# ioboard-right.net
KiCad netlist of a schematic drawn in EAGLE
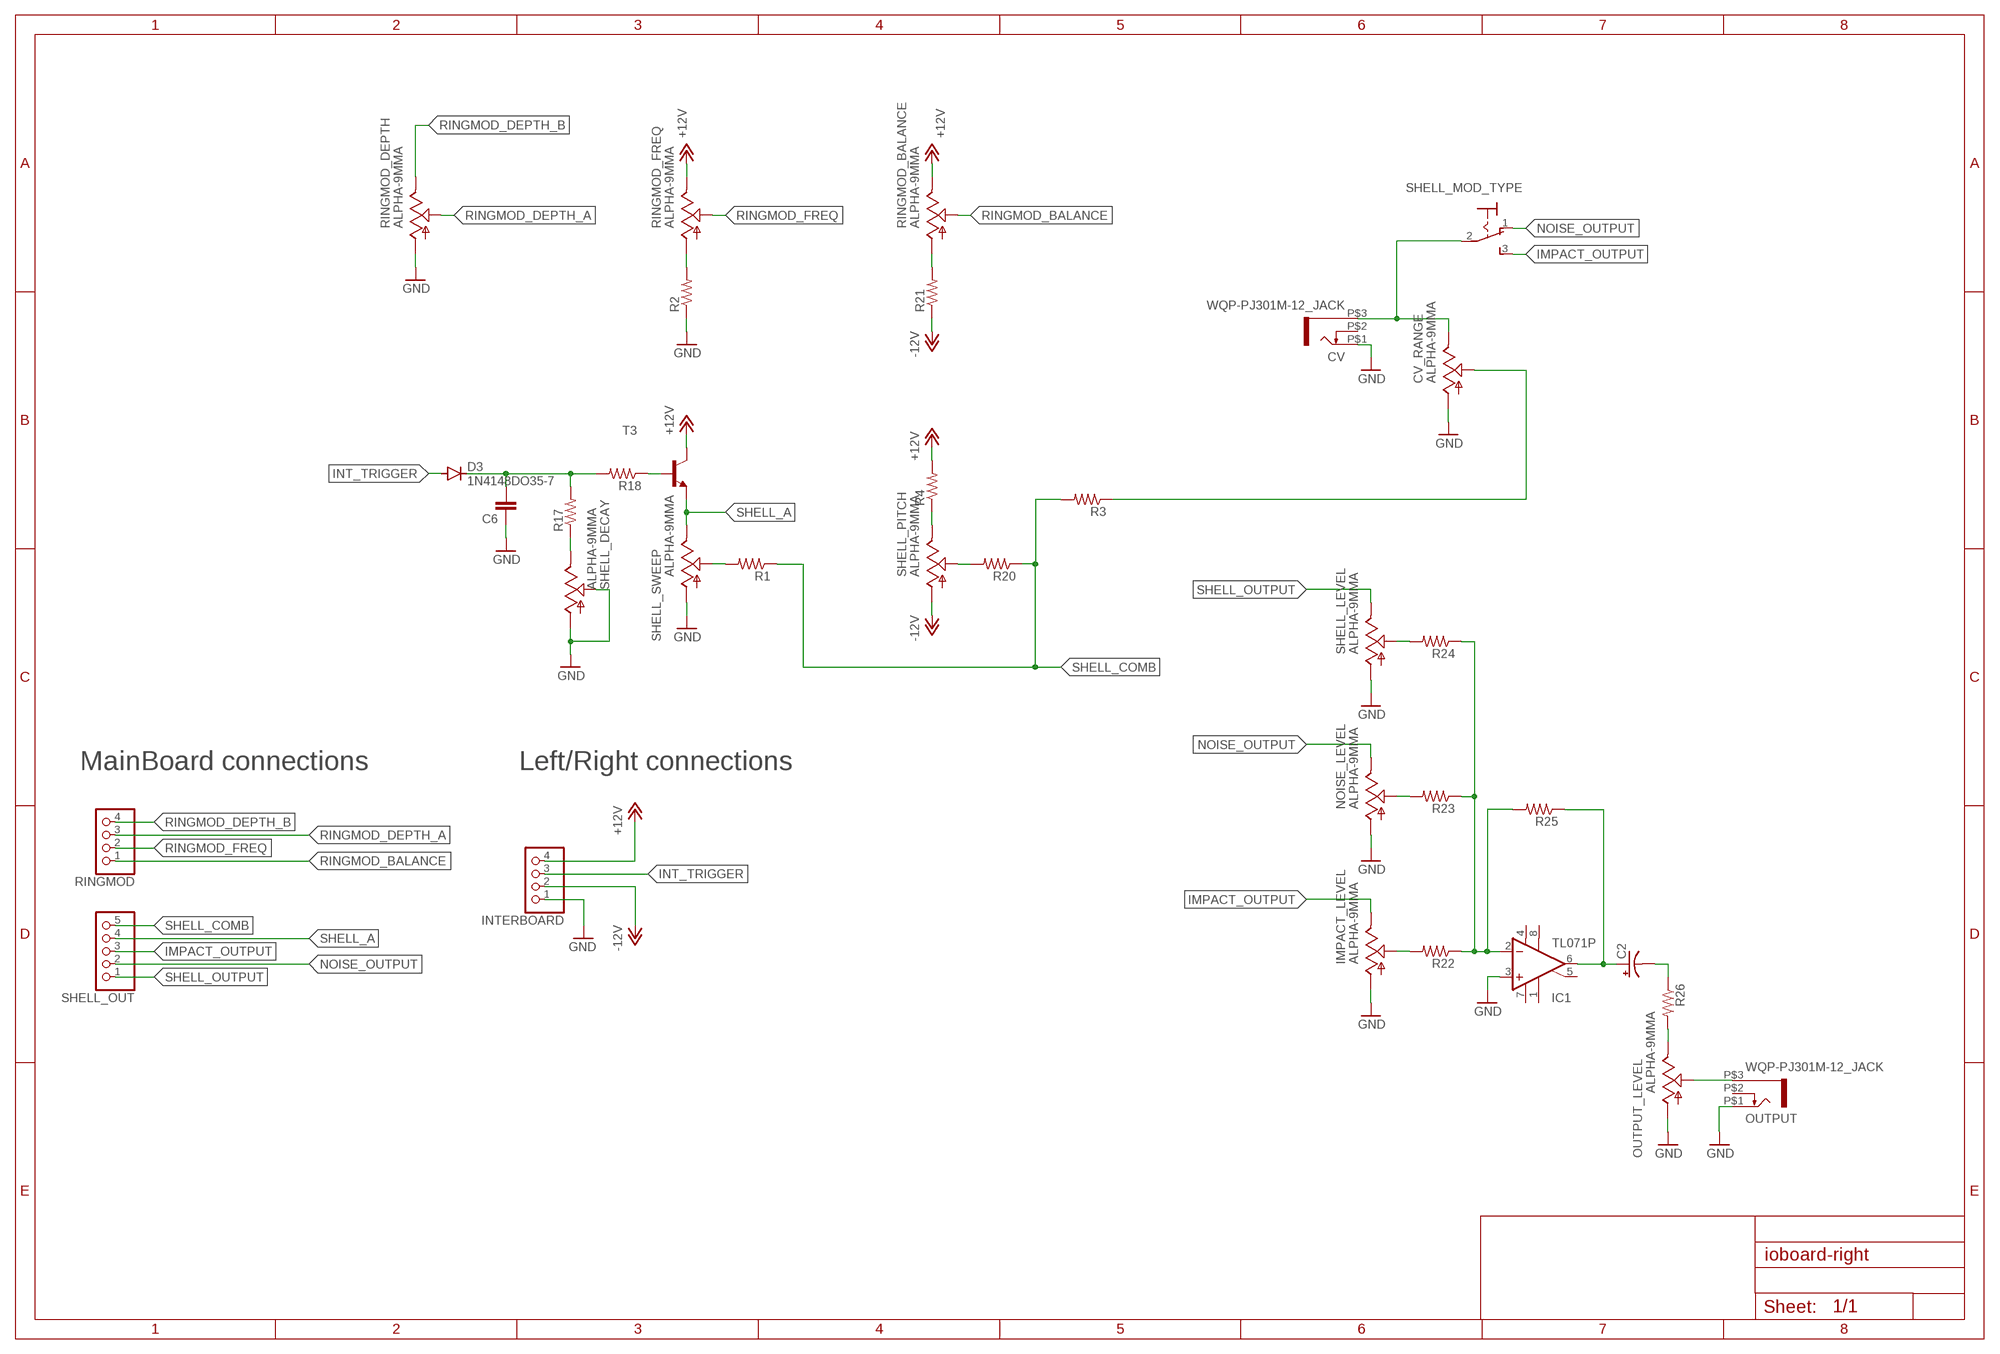
[diagram p0: schematic, sheet 1]

(export (version "E")
  (design (tool "Eeschema 10.0.6"))
  (components
    (comp (ref "C2")
      (value "CPOL-USE2.5-6")
      (footprint "eagle-import:E2,5-6")
      (libsource (lib "eagle-import") (part "CPOL-USE2.5-6"))
    )
    (comp (ref "C6")
      (value "C-EU050-024X044")
      (footprint "eagle-import:C050-024X044")
      (libsource (lib "eagle-import") (part "C-EU050-024X044"))
    )
    (comp (ref "CV")
      (value "WQP-PJ301M-12_JACK")
      (footprint "eagle-import:WQP-PJ301M-12_JACK")
      (libsource (lib "eagle-import") (part "WQP-PJ301M-12_JACK"))
    )
    (comp (ref "CV_RANGE")
      (value "ALPHA-9MMA")
      (footprint "eagle-import:EVUF")
      (libsource (lib "eagle-import") (part "ALPHA-9MMA"))
    )
    (comp (ref "D3")
      (value "1N4148DO35-7")
      (footprint "eagle-import:DO35-7")
      (libsource (lib "eagle-import") (part "1N4148DO35-7"))
    )
    (comp (ref "IC1")
      (value "TL071P")
      (footprint "eagle-import:DIL08")
      (libsource (lib "eagle-import") (part "TL071P"))
    )
    (comp (ref "IMPACT_LEVEL")
      (value "ALPHA-9MMA")
      (footprint "eagle-import:EVUF")
      (libsource (lib "eagle-import") (part "ALPHA-9MMA"))
    )
    (comp (ref "INTERBOARD")
      (value "PINHD-1X4")
      (footprint "eagle-import:1X04")
      (libsource (lib "eagle-import") (part "PINHD-1X4"))
    )
    (comp (ref "NOISE_LEVEL")
      (value "ALPHA-9MMA")
      (footprint "eagle-import:EVUF")
      (libsource (lib "eagle-import") (part "ALPHA-9MMA"))
    )
    (comp (ref "OUTPUT")
      (value "WQP-PJ301M-12_JACK")
      (footprint "eagle-import:WQP-PJ301M-12_JACK")
      (libsource (lib "eagle-import") (part "WQP-PJ301M-12_JACK"))
    )
    (comp (ref "OUTPUT_LEVEL")
      (value "ALPHA-9MMA")
      (footprint "eagle-import:EVUF")
      (libsource (lib "eagle-import") (part "ALPHA-9MMA"))
    )
    (comp (ref "R1")
      (value "R-US_0207/7")
      (footprint "eagle-import:0207_7")
      (libsource (lib "eagle-import") (part "R-US_0207/7"))
    )
    (comp (ref "R2")
      (value "R-US_0207/7")
      (footprint "eagle-import:0207_7")
      (libsource (lib "eagle-import") (part "R-US_0207/7"))
    )
    (comp (ref "R3")
      (value "R-US_0207/7")
      (footprint "eagle-import:0207_7")
      (libsource (lib "eagle-import") (part "R-US_0207/7"))
    )
    (comp (ref "R4")
      (value "R-US_0207/7")
      (footprint "eagle-import:0207_7")
      (libsource (lib "eagle-import") (part "R-US_0207/7"))
    )
    (comp (ref "R17")
      (value "R-US_0207/7")
      (footprint "eagle-import:0207_7")
      (libsource (lib "eagle-import") (part "R-US_0207/7"))
    )
    (comp (ref "R18")
      (value "R-US_0207/7")
      (footprint "eagle-import:0207_7")
      (libsource (lib "eagle-import") (part "R-US_0207/7"))
    )
    (comp (ref "R20")
      (value "R-US_0207/7")
      (footprint "eagle-import:0207_7")
      (libsource (lib "eagle-import") (part "R-US_0207/7"))
    )
    (comp (ref "R21")
      (value "R-US_0207/7")
      (footprint "eagle-import:0207_7")
      (libsource (lib "eagle-import") (part "R-US_0207/7"))
    )
    (comp (ref "R22")
      (value "R-US_0207/7")
      (footprint "eagle-import:0207_7")
      (libsource (lib "eagle-import") (part "R-US_0207/7"))
    )
    (comp (ref "R23")
      (value "R-US_0207/7")
      (footprint "eagle-import:0207_7")
      (libsource (lib "eagle-import") (part "R-US_0207/7"))
    )
    (comp (ref "R24")
      (value "R-US_0207/7")
      (footprint "eagle-import:0207_7")
      (libsource (lib "eagle-import") (part "R-US_0207/7"))
    )
    (comp (ref "R25")
      (value "R-US_0207/7")
      (footprint "eagle-import:0207_7")
      (libsource (lib "eagle-import") (part "R-US_0207/7"))
    )
    (comp (ref "R26")
      (value "R-US_0207/7")
      (footprint "eagle-import:0207_7")
      (libsource (lib "eagle-import") (part "R-US_0207/7"))
    )
    (comp (ref "RINGMOD")
      (value "PINHD-1X4")
      (footprint "eagle-import:1X04")
      (libsource (lib "eagle-import") (part "PINHD-1X4"))
    )
    (comp (ref "RINGMOD_BALANCE")
      (value "ALPHA-9MMA")
      (footprint "eagle-import:EVUF")
      (libsource (lib "eagle-import") (part "ALPHA-9MMA"))
    )
    (comp (ref "RINGMOD_DEPTH")
      (value "ALPHA-9MMA")
      (footprint "eagle-import:EVUF")
      (libsource (lib "eagle-import") (part "ALPHA-9MMA"))
    )
    (comp (ref "RINGMOD_FREQ")
      (value "ALPHA-9MMA")
      (footprint "eagle-import:EVUF")
      (libsource (lib "eagle-import") (part "ALPHA-9MMA"))
    )
    (comp (ref "SHELL_DECAY")
      (value "ALPHA-9MMA")
      (footprint "eagle-import:EVUF")
      (libsource (lib "eagle-import") (part "ALPHA-9MMA"))
    )
    (comp (ref "SHELL_LEVEL")
      (value "ALPHA-9MMA")
      (footprint "eagle-import:EVUF")
      (libsource (lib "eagle-import") (part "ALPHA-9MMA"))
    )
    (comp (ref "SHELL_MOD_TYPE")
      (value "M9040P")
      (footprint "eagle-import:M9040P")
      (libsource (lib "eagle-import") (part "M9040P"))
    )
    (comp (ref "SHELL_OUT")
      (value "PINHD-1X5")
      (footprint "eagle-import:1X05")
      (libsource (lib "eagle-import") (part "PINHD-1X5"))
    )
    (comp (ref "SHELL_PITCH")
      (value "ALPHA-9MMA")
      (footprint "eagle-import:EVUF")
      (libsource (lib "eagle-import") (part "ALPHA-9MMA"))
    )
    (comp (ref "SHELL_SWEEP")
      (value "ALPHA-9MMA")
      (footprint "eagle-import:EVUF")
      (libsource (lib "eagle-import") (part "ALPHA-9MMA"))
    )
    (comp (ref "T3")
      (value "2N3904-NPN-TO92-EBC")
      (footprint "eagle-import:TO92-EBC")
      (libsource (lib "eagle-import") (part "-NPN-TO92-EBC2N3904"))
    )
  )
  (nets
    (net (code "1") (name "+12V") (class "Default")
      (node (ref "INTERBOARD") (pin "4") (pinfunction "4_4") (pintype "passive"))
      (node (ref "R4") (pin "2") (pinfunction "2_2") (pintype "passive"))
      (node (ref "RINGMOD_BALANCE") (pin "3") (pinfunction "E_3") (pintype "passive"))
      (node (ref "RINGMOD_FREQ") (pin "3") (pinfunction "E_3") (pintype "passive"))
      (node (ref "T3") (pin "C") (pinfunction "C_C") (pintype "passive"))
    )
    (net (code "2") (name "-12V") (class "Default")
      (node (ref "INTERBOARD") (pin "2") (pinfunction "2_2") (pintype "passive"))
      (node (ref "R21") (pin "1") (pinfunction "1_1") (pintype "passive"))
      (node (ref "SHELL_PITCH") (pin "1") (pinfunction "A_1") (pintype "passive"))
    )
    (net (code "3") (name "/V+") (class "Default")
      (node (ref "IC1") (pin "7") (pinfunction "V+_7") (pintype "power_in"))
    )
    (net (code "4") (name "/V-") (class "Default")
      (node (ref "IC1") (pin "4") (pinfunction "V-_4") (pintype "power_in"))
    )
    (net (code "5") (name "GND") (class "Default")
      (node (ref "C6") (pin "1") (pinfunction "1_1") (pintype "passive"))
      (node (ref "CV") (pin "P$1") (pinfunction "2_P$1") (pintype "passive"))
      (node (ref "CV_RANGE") (pin "1") (pinfunction "A_1") (pintype "passive"))
      (node (ref "IC1") (pin "3") (pinfunction "+IN_3") (pintype "input"))
      (node (ref "IMPACT_LEVEL") (pin "1") (pinfunction "A_1") (pintype "passive"))
      (node (ref "INTERBOARD") (pin "1") (pinfunction "1_1") (pintype "passive"))
      (node (ref "NOISE_LEVEL") (pin "1") (pinfunction "A_1") (pintype "passive"))
      (node (ref "OUTPUT") (pin "P$1") (pinfunction "2_P$1") (pintype "passive"))
      (node (ref "OUTPUT_LEVEL") (pin "1") (pinfunction "A_1") (pintype "passive"))
      (node (ref "R2") (pin "1") (pinfunction "1_1") (pintype "passive"))
      (node (ref "RINGMOD_DEPTH") (pin "1") (pinfunction "A_1") (pintype "passive"))
      (node (ref "SHELL_DECAY") (pin "1") (pinfunction "A_1") (pintype "passive"))
      (node (ref "SHELL_DECAY") (pin "2") (pinfunction "S_2") (pintype "passive"))
      (node (ref "SHELL_LEVEL") (pin "1") (pinfunction "A_1") (pintype "passive"))
      (node (ref "SHELL_SWEEP") (pin "1") (pinfunction "A_1") (pintype "passive"))
    )
    (net (code "6") (name "IMPACT_OUTPUT") (class "Default")
      (node (ref "IMPACT_LEVEL") (pin "3") (pinfunction "E_3") (pintype "passive"))
      (node (ref "SHELL_MOD_TYPE") (pin "3") (pinfunction "S_3") (pintype "passive"))
      (node (ref "SHELL_OUT") (pin "3") (pinfunction "3_3") (pintype "passive"))
    )
    (net (code "7") (name "INT_TRIGGER") (class "Default")
      (node (ref "D3") (pin "A") (pinfunction "A_A") (pintype "passive"))
      (node (ref "INTERBOARD") (pin "3") (pinfunction "3_3") (pintype "passive"))
    )
    (net (code "8") (name "NOISE_OUTPUT") (class "Default")
      (node (ref "NOISE_LEVEL") (pin "3") (pinfunction "E_3") (pintype "passive"))
      (node (ref "SHELL_MOD_TYPE") (pin "1") (pinfunction "O_1") (pintype "passive"))
      (node (ref "SHELL_OUT") (pin "2") (pinfunction "2_2") (pintype "passive"))
    )
    (net (code "9") (name "Net-(C2-Pad-)") (class "Default")
      (node (ref "C2") (pin "-") (pinfunction "-_-") (pintype "passive"))
      (node (ref "R26") (pin "1") (pinfunction "1_1") (pintype "passive"))
    )
    (net (code "10") (name "Net-(C6-Pad2)") (class "Default")
      (node (ref "C6") (pin "2") (pinfunction "2_2") (pintype "passive"))
      (node (ref "D3") (pin "C") (pinfunction "C_C") (pintype "passive"))
      (node (ref "R17") (pin "2") (pinfunction "2_2") (pintype "passive"))
      (node (ref "R18") (pin "2") (pinfunction "2_2") (pintype "passive"))
    )
    (net (code "11") (name "Net-(CV-1)") (class "Default")
      (node (ref "CV") (pin "P$3") (pinfunction "1_P$3") (pintype "passive"))
      (node (ref "CV_RANGE") (pin "3") (pinfunction "E_3") (pintype "passive"))
      (node (ref "SHELL_MOD_TYPE") (pin "2") (pinfunction "P_2") (pintype "passive"))
    )
    (net (code "12") (name "Net-(CV_RANGE-S)") (class "Default")
      (node (ref "CV_RANGE") (pin "2") (pinfunction "S_2") (pintype "passive"))
      (node (ref "R3") (pin "1") (pinfunction "1_1") (pintype "passive"))
    )
    (net (code "13") (name "Net-(IC1--IN)") (class "Default")
      (node (ref "IC1") (pin "2") (pinfunction "-IN_2") (pintype "input"))
      (node (ref "R22") (pin "1") (pinfunction "1_1") (pintype "passive"))
      (node (ref "R23") (pin "1") (pinfunction "1_1") (pintype "passive"))
      (node (ref "R24") (pin "1") (pinfunction "1_1") (pintype "passive"))
      (node (ref "R25") (pin "2") (pinfunction "2_2") (pintype "passive"))
    )
    (net (code "14") (name "Net-(IC1-OUT)") (class "Default")
      (node (ref "C2") (pin "+") (pinfunction "+_+") (pintype "passive"))
      (node (ref "IC1") (pin "6") (pinfunction "OUT_6") (pintype "output"))
      (node (ref "R25") (pin "1") (pinfunction "1_1") (pintype "passive"))
    )
    (net (code "15") (name "Net-(IMPACT_LEVEL-S)") (class "Default")
      (node (ref "IMPACT_LEVEL") (pin "2") (pinfunction "S_2") (pintype "passive"))
      (node (ref "R22") (pin "2") (pinfunction "2_2") (pintype "passive"))
    )
    (net (code "16") (name "Net-(NOISE_LEVEL-S)") (class "Default")
      (node (ref "NOISE_LEVEL") (pin "2") (pinfunction "S_2") (pintype "passive"))
      (node (ref "R23") (pin "2") (pinfunction "2_2") (pintype "passive"))
    )
    (net (code "17") (name "Net-(OUTPUT-1)") (class "Default")
      (node (ref "OUTPUT") (pin "P$3") (pinfunction "1_P$3") (pintype "passive"))
      (node (ref "OUTPUT_LEVEL") (pin "2") (pinfunction "S_2") (pintype "passive"))
    )
    (net (code "18") (name "Net-(OUTPUT_LEVEL-E)") (class "Default")
      (node (ref "OUTPUT_LEVEL") (pin "3") (pinfunction "E_3") (pintype "passive"))
      (node (ref "R26") (pin "2") (pinfunction "2_2") (pintype "passive"))
    )
    (net (code "19") (name "Net-(R18-Pad1)") (class "Default")
      (node (ref "R18") (pin "1") (pinfunction "1_1") (pintype "passive"))
      (node (ref "T3") (pin "B") (pinfunction "B_B") (pintype "passive"))
    )
    (net (code "20") (name "Net-(RINGMOD_BALANCE-A)") (class "Default")
      (node (ref "R21") (pin "2") (pinfunction "2_2") (pintype "passive"))
      (node (ref "RINGMOD_BALANCE") (pin "1") (pinfunction "A_1") (pintype "passive"))
    )
    (net (code "21") (name "Net-(RINGMOD_FREQ-A)") (class "Default")
      (node (ref "R2") (pin "2") (pinfunction "2_2") (pintype "passive"))
      (node (ref "RINGMOD_FREQ") (pin "1") (pinfunction "A_1") (pintype "passive"))
    )
    (net (code "22") (name "Net-(SHELL_DECAY-E)") (class "Default")
      (node (ref "R17") (pin "1") (pinfunction "1_1") (pintype "passive"))
      (node (ref "SHELL_DECAY") (pin "3") (pinfunction "E_3") (pintype "passive"))
    )
    (net (code "23") (name "Net-(SHELL_LEVEL-S)") (class "Default")
      (node (ref "R24") (pin "2") (pinfunction "2_2") (pintype "passive"))
      (node (ref "SHELL_LEVEL") (pin "2") (pinfunction "S_2") (pintype "passive"))
    )
    (net (code "24") (name "Net-(SHELL_PITCH-E)") (class "Default")
      (node (ref "R4") (pin "1") (pinfunction "1_1") (pintype "passive"))
      (node (ref "SHELL_PITCH") (pin "3") (pinfunction "E_3") (pintype "passive"))
    )
    (net (code "25") (name "Net-(SHELL_PITCH-S)") (class "Default")
      (node (ref "R20") (pin "2") (pinfunction "2_2") (pintype "passive"))
      (node (ref "SHELL_PITCH") (pin "2") (pinfunction "S_2") (pintype "passive"))
    )
    (net (code "26") (name "Net-(SHELL_SWEEP-S)") (class "Default")
      (node (ref "R1") (pin "2") (pinfunction "2_2") (pintype "passive"))
      (node (ref "SHELL_SWEEP") (pin "2") (pinfunction "S_2") (pintype "passive"))
    )
    (net (code "27") (name "RINGMOD_BALANCE") (class "Default")
      (node (ref "RINGMOD") (pin "1") (pinfunction "1_1") (pintype "passive"))
      (node (ref "RINGMOD_BALANCE") (pin "2") (pinfunction "S_2") (pintype "passive"))
    )
    (net (code "28") (name "RINGMOD_DEPTH_A") (class "Default")
      (node (ref "RINGMOD") (pin "3") (pinfunction "3_3") (pintype "passive"))
      (node (ref "RINGMOD_DEPTH") (pin "2") (pinfunction "S_2") (pintype "passive"))
    )
    (net (code "29") (name "RINGMOD_DEPTH_B") (class "Default")
      (node (ref "RINGMOD") (pin "4") (pinfunction "4_4") (pintype "passive"))
      (node (ref "RINGMOD_DEPTH") (pin "3") (pinfunction "E_3") (pintype "passive"))
    )
    (net (code "30") (name "RINGMOD_FREQ") (class "Default")
      (node (ref "RINGMOD") (pin "2") (pinfunction "2_2") (pintype "passive"))
      (node (ref "RINGMOD_FREQ") (pin "2") (pinfunction "S_2") (pintype "passive"))
    )
    (net (code "31") (name "SHELL_A") (class "Default")
      (node (ref "SHELL_OUT") (pin "4") (pinfunction "4_4") (pintype "passive"))
      (node (ref "SHELL_SWEEP") (pin "3") (pinfunction "E_3") (pintype "passive"))
      (node (ref "T3") (pin "E") (pinfunction "E_E") (pintype "passive"))
    )
    (net (code "32") (name "SHELL_COMB") (class "Default")
      (node (ref "R1") (pin "1") (pinfunction "1_1") (pintype "passive"))
      (node (ref "R20") (pin "1") (pinfunction "1_1") (pintype "passive"))
      (node (ref "R3") (pin "2") (pinfunction "2_2") (pintype "passive"))
      (node (ref "SHELL_OUT") (pin "5") (pinfunction "5_5") (pintype "passive"))
    )
    (net (code "33") (name "SHELL_OUTPUT") (class "Default")
      (node (ref "SHELL_LEVEL") (pin "3") (pinfunction "E_3") (pintype "passive"))
      (node (ref "SHELL_OUT") (pin "1") (pinfunction "1_1") (pintype "passive"))
    )
    (net (code "34") (name "unconnected-(CV-3-PadP$2)") (class "Default")
      (node (ref "CV") (pin "P$2") (pinfunction "3_P$2") (pintype "passive"))
    )
    (net (code "35") (name "unconnected-(IC1-ON1-Pad1)") (class "Default")
      (node (ref "IC1") (pin "1") (pinfunction "ON1_1") (pintype "passive"))
    )
    (net (code "36") (name "unconnected-(IC1-ON2-Pad5)") (class "Default")
      (node (ref "IC1") (pin "5") (pinfunction "ON2_5") (pintype "passive"))
    )
    (net (code "37") (name "unconnected-(IC1-OPT-Pad8)") (class "Default")
      (node (ref "IC1") (pin "8") (pinfunction "OPT_8") (pintype "passive"))
    )
    (net (code "38") (name "unconnected-(OUTPUT-3-PadP$2)") (class "Default")
      (node (ref "OUTPUT") (pin "P$2") (pinfunction "3_P$2") (pintype "passive"))
    )
  )
)
